# Single_Cell.net
KiCad netlist of a schematic drawn in EAGLE
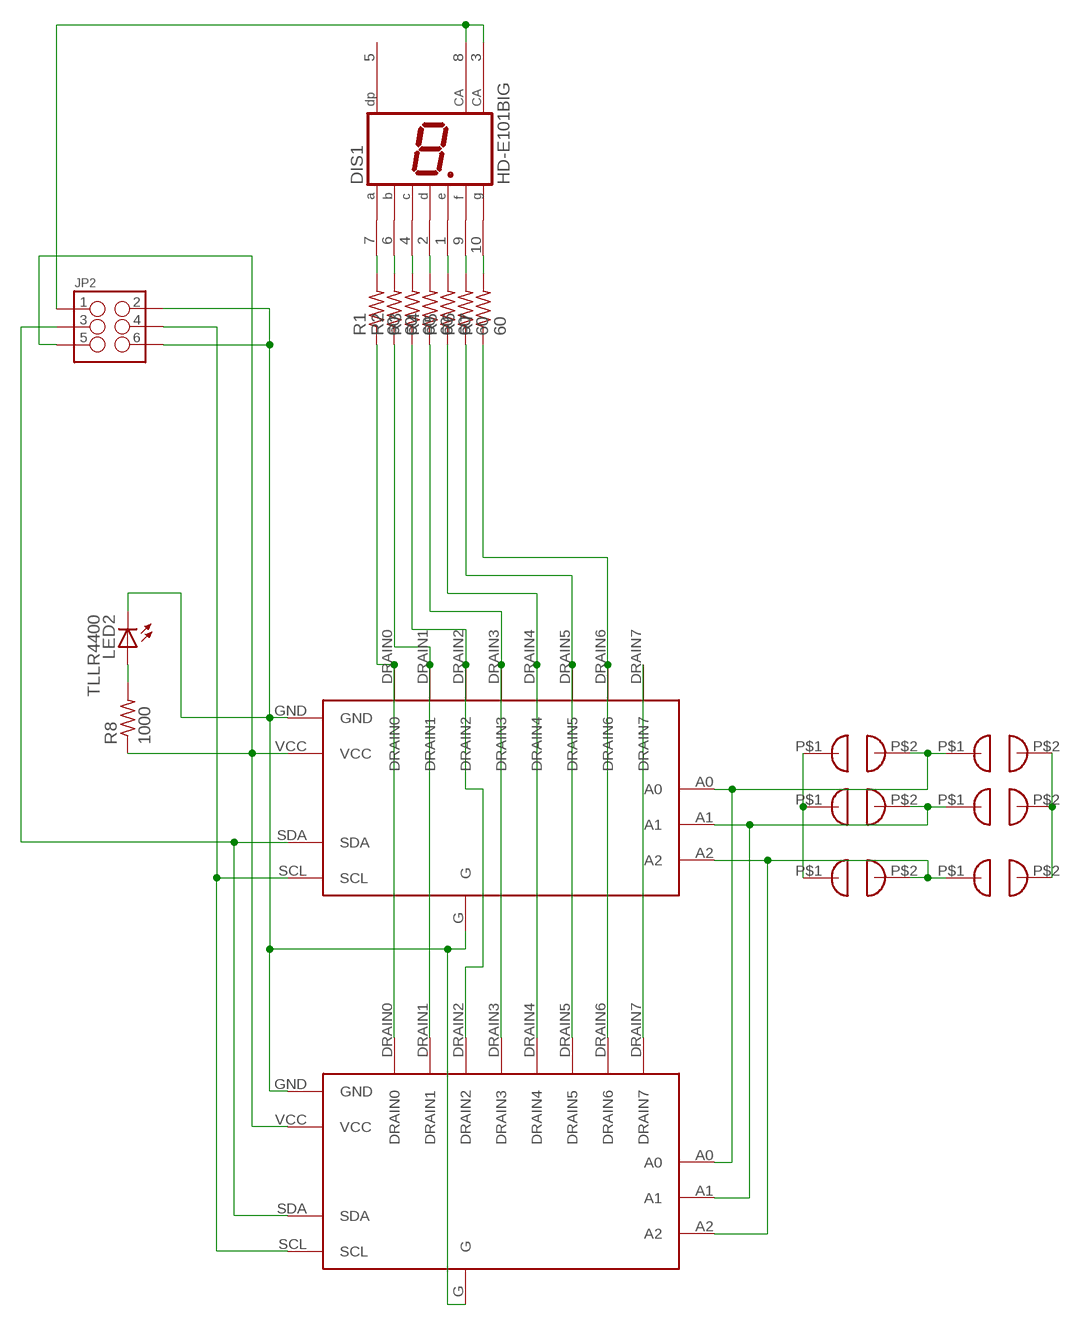
[diagram p0: schematic, sheet 1]

(export (version "E")
  (design (tool "Eeschema 10.0.6"))
  (components
    (comp (ref "DIS1")
      (value "HD-E101BIG")
      (footprint "eagle-import:7SEGMENT_BACKWARDS")
      (libsource (lib "eagle-import") (part "HD-E101BACKWARDS"))
    )
    (comp (ref "JP2")
      (value "M03X2SHROUD")
      (footprint "eagle-import:2X3-SHROUDED")
      (fields (field (name "PROD_ID") "CONN-10681"))
      (libsource (lib "eagle-import") (part "M03X2SHROUD"))
    )
    (comp (ref "LED2")
      (value "TLLR4400")
      (footprint "eagle-import:LED3MM")
      (fields
        (field (name "MF") "VISHAY SEMICONDUCTOR")
        (field (name "MF_1") "VISHAY SEMICONDUCTOR")
        (field (name "OC_FARNELL") "1612437")
      )
      (libsource (lib "eagle-import") (part "TLLR4400"))
    )
    (comp (ref "R1")
      (value "60")
      (footprint "eagle-import:0207_15")
      (libsource (lib "eagle-import") (part "R-US_0207/15"))
    )
    (comp (ref "R2")
      (value "60")
      (footprint "eagle-import:0207_15")
      (libsource (lib "eagle-import") (part "R-US_0207/15"))
    )
    (comp (ref "R3")
      (value "60")
      (footprint "eagle-import:0207_15")
      (libsource (lib "eagle-import") (part "R-US_0207/15"))
    )
    (comp (ref "R4")
      (value "60")
      (footprint "eagle-import:0207_15")
      (libsource (lib "eagle-import") (part "R-US_0207/15"))
    )
    (comp (ref "R5")
      (value "60")
      (footprint "eagle-import:0207_15")
      (libsource (lib "eagle-import") (part "R-US_0207/15"))
    )
    (comp (ref "R6")
      (value "60")
      (footprint "eagle-import:0207_15")
      (libsource (lib "eagle-import") (part "R-US_0207/15"))
    )
    (comp (ref "R7")
      (value "60")
      (footprint "eagle-import:0207_15")
      (libsource (lib "eagle-import") (part "R-US_0207/15"))
    )
    (comp (ref "R8")
      (value "1000")
      (footprint "eagle-import:0207_15")
      (libsource (lib "eagle-import") (part "R-US_0207/15"))
    )
    (comp (ref "U$1")
      (value "SOLDER_JUMPER")
      (footprint "eagle-import:SOLDER_JUMPER")
      (libsource (lib "eagle-import") (part "SOLDER_JUMPER"))
    )
    (comp (ref "U$2")
      (value "LED_DRIVERBOARDADAFRUIT")
      (footprint "eagle-import:DRIVER_BOARD_ADAFRUIT")
      (libsource (lib "eagle-import") (part "LED_DRIVERBOARDADAFRUIT"))
    )
    (comp (ref "U$3")
      (value "SOLDER_JUMPER")
      (footprint "eagle-import:SOLDER_JUMPER")
      (libsource (lib "eagle-import") (part "SOLDER_JUMPER"))
    )
    (comp (ref "U$4")
      (value "SOLDER_JUMPER")
      (footprint "eagle-import:SOLDER_JUMPER")
      (libsource (lib "eagle-import") (part "SOLDER_JUMPER"))
    )
    (comp (ref "U$5")
      (value "SOLDER_JUMPER")
      (footprint "eagle-import:SOLDER_JUMPER")
      (libsource (lib "eagle-import") (part "SOLDER_JUMPER"))
    )
    (comp (ref "U$6")
      (value "SOLDER_JUMPER")
      (footprint "eagle-import:SOLDER_JUMPER")
      (libsource (lib "eagle-import") (part "SOLDER_JUMPER"))
    )
    (comp (ref "U$7")
      (value "SOLDER_JUMPER")
      (footprint "eagle-import:SOLDER_JUMPER")
      (libsource (lib "eagle-import") (part "SOLDER_JUMPER"))
    )
    (comp (ref "U$8")
      (value "LED_DRIVERBOARD")
      (footprint "eagle-import:DRIVER_BOARD")
      (libsource (lib "eagle-import") (part "LED_DRIVERBOARD"))
    )
  )
  (nets
    (net (code "1") (name "/GND") (class "Default")
      (node (ref "JP2") (pin "2") (pinfunction "2_2") (pintype "bidirectional"))
      (node (ref "JP2") (pin "6") (pinfunction "6_6") (pintype "bidirectional"))
      (node (ref "LED2") (pin "K") (pinfunction "C_K") (pintype "passive"))
      (node (ref "U$1") (pin "P$1") (pinfunction "P$3_P$1") (pintype "bidirectional"))
      (node (ref "U$2") (pin "G") (pinfunction "G_G") (pintype "bidirectional"))
      (node (ref "U$2") (pin "GND") (pinfunction "GND_GND") (pintype "bidirectional"))
      (node (ref "U$4") (pin "P$1") (pinfunction "P$3_P$1") (pintype "bidirectional"))
      (node (ref "U$6") (pin "P$1") (pinfunction "P$3_P$1") (pintype "bidirectional"))
      (node (ref "U$8") (pin "G") (pinfunction "G_G") (pintype "bidirectional"))
      (node (ref "U$8") (pin "GND") (pinfunction "GND_GND") (pintype "bidirectional"))
    )
    (net (code "2") (name "/VCC5") (class "Default")
      (node (ref "JP2") (pin "5") (pinfunction "5_5") (pintype "bidirectional"))
      (node (ref "R8") (pin "1") (pinfunction "1_1") (pintype "passive"))
      (node (ref "U$2") (pin "VCC") (pinfunction "VCC_VCC") (pintype "bidirectional"))
      (node (ref "U$3") (pin "P$2") (pinfunction "P$4_P$2") (pintype "bidirectional"))
      (node (ref "U$5") (pin "P$2") (pinfunction "P$4_P$2") (pintype "bidirectional"))
      (node (ref "U$7") (pin "P$2") (pinfunction "P$4_P$2") (pintype "bidirectional"))
      (node (ref "U$8") (pin "VCC") (pinfunction "VCC_VCC") (pintype "bidirectional"))
    )
    (net (code "3") (name "Net-(DIS1-A)") (class "Default")
      (node (ref "DIS1") (pin "7") (pinfunction "A_7") (pintype "passive"))
      (node (ref "R1") (pin "2") (pinfunction "2_2") (pintype "passive"))
    )
    (net (code "4") (name "Net-(DIS1-B)") (class "Default")
      (node (ref "DIS1") (pin "6") (pinfunction "B_6") (pintype "passive"))
      (node (ref "R2") (pin "2") (pinfunction "2_2") (pintype "passive"))
    )
    (net (code "5") (name "Net-(DIS1-C)") (class "Default")
      (node (ref "DIS1") (pin "4") (pinfunction "C_4") (pintype "passive"))
      (node (ref "R3") (pin "2") (pinfunction "2_2") (pintype "passive"))
    )
    (net (code "6") (name "Net-(DIS1-CA-Pad3)") (class "Default")
      (node (ref "DIS1") (pin "3") (pinfunction "CA_3") (pintype "passive"))
      (node (ref "DIS1") (pin "8") (pinfunction "CA_8") (pintype "passive"))
      (node (ref "JP2") (pin "1") (pinfunction "1_1") (pintype "bidirectional"))
    )
    (net (code "7") (name "Net-(DIS1-D)") (class "Default")
      (node (ref "DIS1") (pin "2") (pinfunction "D_2") (pintype "passive"))
      (node (ref "R4") (pin "2") (pinfunction "2_2") (pintype "passive"))
    )
    (net (code "8") (name "Net-(DIS1-E)") (class "Default")
      (node (ref "DIS1") (pin "1") (pinfunction "E_1") (pintype "passive"))
      (node (ref "R5") (pin "2") (pinfunction "2_2") (pintype "passive"))
    )
    (net (code "9") (name "Net-(DIS1-F)") (class "Default")
      (node (ref "DIS1") (pin "9") (pinfunction "F_9") (pintype "passive"))
      (node (ref "R6") (pin "2") (pinfunction "2_2") (pintype "passive"))
    )
    (net (code "10") (name "Net-(DIS1-G)") (class "Default")
      (node (ref "DIS1") (pin "10") (pinfunction "G_10") (pintype "passive"))
      (node (ref "R7") (pin "2") (pinfunction "2_2") (pintype "passive"))
    )
    (net (code "11") (name "Net-(JP2-Pad3)") (class "Default")
      (node (ref "JP2") (pin "3") (pinfunction "3_3") (pintype "bidirectional"))
      (node (ref "U$2") (pin "SDA") (pinfunction "SDA_SDA") (pintype "bidirectional"))
      (node (ref "U$8") (pin "SDA") (pinfunction "SDA_SDA") (pintype "bidirectional"))
    )
    (net (code "12") (name "Net-(JP2-Pad4)") (class "Default")
      (node (ref "JP2") (pin "4") (pinfunction "4_4") (pintype "bidirectional"))
      (node (ref "U$2") (pin "SCL") (pinfunction "SCL_SCL") (pintype "bidirectional"))
      (node (ref "U$8") (pin "SCL") (pinfunction "SCL_SCL") (pintype "bidirectional"))
    )
    (net (code "13") (name "Net-(LED2-PadA)") (class "Default")
      (node (ref "LED2") (pin "A") (pinfunction "A_A") (pintype "passive"))
      (node (ref "R8") (pin "2") (pinfunction "2_2") (pintype "passive"))
    )
    (net (code "14") (name "Net-(R1-Pad1)") (class "Default")
      (node (ref "R1") (pin "1") (pinfunction "1_1") (pintype "passive"))
      (node (ref "U$2") (pin "DRAIN0") (pinfunction "DRAIN0_DRAIN0") (pintype "bidirectional"))
      (node (ref "U$8") (pin "DRAIN0") (pinfunction "DRAIN0_DRAIN0") (pintype "bidirectional"))
    )
    (net (code "15") (name "Net-(R2-Pad1)") (class "Default")
      (node (ref "R2") (pin "1") (pinfunction "1_1") (pintype "passive"))
      (node (ref "U$2") (pin "DRAIN1") (pinfunction "DRAIN1_DRAIN1") (pintype "bidirectional"))
      (node (ref "U$8") (pin "DRAIN1") (pinfunction "DRAIN1_DRAIN1") (pintype "bidirectional"))
    )
    (net (code "16") (name "Net-(R3-Pad1)") (class "Default")
      (node (ref "R3") (pin "1") (pinfunction "1_1") (pintype "passive"))
      (node (ref "U$2") (pin "DRAIN2") (pinfunction "DRAIN2_DRAIN2") (pintype "bidirectional"))
      (node (ref "U$8") (pin "DRAIN2") (pinfunction "DRAIN2_DRAIN2") (pintype "bidirectional"))
    )
    (net (code "17") (name "Net-(R4-Pad1)") (class "Default")
      (node (ref "R4") (pin "1") (pinfunction "1_1") (pintype "passive"))
      (node (ref "U$2") (pin "DRAIN3") (pinfunction "DRAIN3_DRAIN3") (pintype "bidirectional"))
      (node (ref "U$8") (pin "DRAIN3") (pinfunction "DRAIN3_DRAIN3") (pintype "bidirectional"))
    )
    (net (code "18") (name "Net-(R5-Pad1)") (class "Default")
      (node (ref "R5") (pin "1") (pinfunction "1_1") (pintype "passive"))
      (node (ref "U$2") (pin "DRAIN4") (pinfunction "DRAIN4_DRAIN4") (pintype "bidirectional"))
      (node (ref "U$8") (pin "DRAIN4") (pinfunction "DRAIN4_DRAIN4") (pintype "bidirectional"))
    )
    (net (code "19") (name "Net-(R6-Pad1)") (class "Default")
      (node (ref "R6") (pin "1") (pinfunction "1_1") (pintype "passive"))
      (node (ref "U$2") (pin "DRAIN5") (pinfunction "DRAIN5_DRAIN5") (pintype "bidirectional"))
      (node (ref "U$8") (pin "DRAIN5") (pinfunction "DRAIN5_DRAIN5") (pintype "bidirectional"))
    )
    (net (code "20") (name "Net-(R7-Pad1)") (class "Default")
      (node (ref "R7") (pin "1") (pinfunction "1_1") (pintype "passive"))
      (node (ref "U$2") (pin "DRAIN6") (pinfunction "DRAIN6_DRAIN6") (pintype "bidirectional"))
      (node (ref "U$8") (pin "DRAIN6") (pinfunction "DRAIN6_DRAIN6") (pintype "bidirectional"))
    )
    (net (code "21") (name "Net-(U$1-P$4)") (class "Default")
      (node (ref "U$1") (pin "P$2") (pinfunction "P$4_P$2") (pintype "bidirectional"))
      (node (ref "U$2") (pin "A0") (pinfunction "A0_A0") (pintype "bidirectional"))
      (node (ref "U$3") (pin "P$1") (pinfunction "P$3_P$1") (pintype "bidirectional"))
      (node (ref "U$8") (pin "A0") (pinfunction "A0_A0") (pintype "bidirectional"))
    )
    (net (code "22") (name "Net-(U$2-PadDRAIN7)") (class "Default")
      (node (ref "U$2") (pin "DRAIN7") (pinfunction "DRAIN7_DRAIN7") (pintype "bidirectional"))
      (node (ref "U$8") (pin "DRAIN7") (pinfunction "DRAIN7_DRAIN7") (pintype "bidirectional"))
    )
    (net (code "23") (name "Net-(U$4-P$4)") (class "Default")
      (node (ref "U$2") (pin "A1") (pinfunction "A1_A1") (pintype "bidirectional"))
      (node (ref "U$4") (pin "P$2") (pinfunction "P$4_P$2") (pintype "bidirectional"))
      (node (ref "U$5") (pin "P$1") (pinfunction "P$3_P$1") (pintype "bidirectional"))
      (node (ref "U$8") (pin "A1") (pinfunction "A1_A1") (pintype "bidirectional"))
    )
    (net (code "24") (name "Net-(U$6-P$4)") (class "Default")
      (node (ref "U$2") (pin "A2") (pinfunction "A2_A2") (pintype "bidirectional"))
      (node (ref "U$6") (pin "P$2") (pinfunction "P$4_P$2") (pintype "bidirectional"))
      (node (ref "U$7") (pin "P$1") (pinfunction "P$3_P$1") (pintype "bidirectional"))
      (node (ref "U$8") (pin "A2") (pinfunction "A2_A2") (pintype "bidirectional"))
    )
    (net (code "25") (name "unconnected-(DIS1-DP-Pad5)") (class "Default")
      (node (ref "DIS1") (pin "5") (pinfunction "DP_5") (pintype "passive"))
    )
  )
)
